# PCIe_USB30.net
KiCad netlist of a schematic drawn in Altium Designer
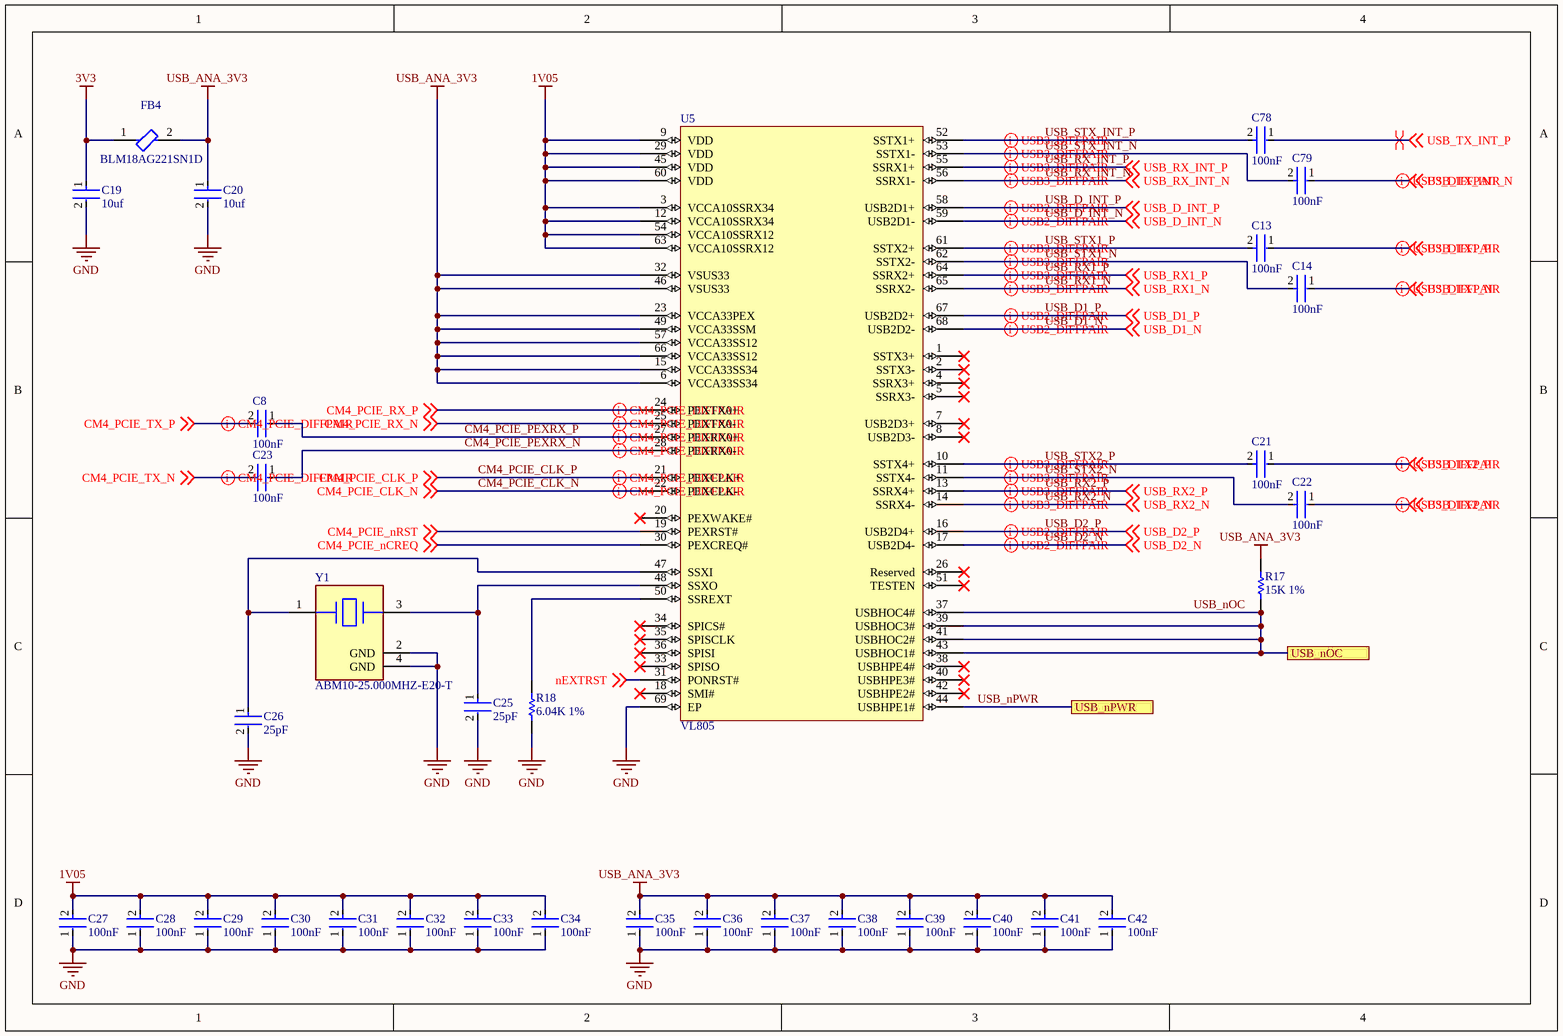
[diagram p0: PCIe_USB30.SchDoc]

(export (version "E")
  (design (tool "Eeschema 10.0.6"))
  (components
    (comp (ref "C8")
      (value "100nF")
      (footprint "FP-GRM15-MFG")
      (description "CAP CER 0.1UF 16V X7R 0402")
      (fields (field (name "MANUFACTURER PART NUMBER") "GRM155R71C104KA88D") (field (name "TOLERANCE") "10%"))
      (libsource (lib "Altium Content Vault") (part "236180d848d6139a670b325ea6854c9"))
    )
    (comp (ref "C13")
      (value "100nF")
      (footprint "FP-GRM15-MFG")
      (description "CAP CER 0.1UF 16V X7R 0402")
      (fields (field (name "MANUFACTURER PART NUMBER") "GRM155R71C104KA88D") (field (name "TOLERANCE") "10%"))
      (libsource (lib "Altium Content Vault") (part "236180d848d6139a670b325ea6854c9"))
    )
    (comp (ref "C14")
      (value "100nF")
      (footprint "FP-GRM15-MFG")
      (description "CAP CER 0.1UF 16V X7R 0402")
      (fields (field (name "MANUFACTURER PART NUMBER") "GRM155R71C104KA88D") (field (name "TOLERANCE") "10%"))
      (libsource (lib "Altium Content Vault") (part "236180d848d6139a670b325ea6854c9"))
    )
    (comp (ref "C19")
      (value "10uf")
      (footprint "FP-GRM188-0_2-IPC_C")
      (description "Chip Multilayer Ceramic Capacitors for General Purpose, 0603, 10uF, X5R, 15%, 20%, 35V")
      (fields (field (name "TOLERANCE") "20%"))
      (libsource (lib "Altium Content Vault") (part "11868f565c42a9108669ba33697ecf6"))
    )
    (comp (ref "C20")
      (value "10uf")
      (footprint "FP-GRM188-0_2-IPC_C")
      (description "Chip Multilayer Ceramic Capacitors for General Purpose, 0603, 10uF, X5R, 15%, 20%, 35V")
      (fields (field (name "TOLERANCE") "20%"))
      (libsource (lib "Altium Content Vault") (part "11868f565c42a9108669ba33697ecf6"))
    )
    (comp (ref "C21")
      (value "100nF")
      (footprint "FP-GRM15-MFG")
      (description "CAP CER 0.1UF 16V X7R 0402")
      (fields (field (name "MANUFACTURER PART NUMBER") "GRM155R71C104KA88D") (field (name "TOLERANCE") "10%"))
      (libsource (lib "Altium Content Vault") (part "236180d848d6139a670b325ea6854c9"))
    )
    (comp (ref "C22")
      (value "100nF")
      (footprint "FP-GRM15-MFG")
      (description "CAP CER 0.1UF 16V X7R 0402")
      (fields (field (name "MANUFACTURER PART NUMBER") "GRM155R71C104KA88D") (field (name "TOLERANCE") "10%"))
      (libsource (lib "Altium Content Vault") (part "236180d848d6139a670b325ea6854c9"))
    )
    (comp (ref "C23")
      (value "100nF")
      (footprint "FP-GRM15-MFG")
      (description "CAP CER 0.1UF 16V X7R 0402")
      (fields (field (name "MANUFACTURER PART NUMBER") "GRM155R71C104KA88D") (field (name "TOLERANCE") "10%"))
      (libsource (lib "Altium Content Vault") (part "236180d848d6139a670b325ea6854c9"))
    )
    (comp (ref "C25")
      (value "25pF")
      (footprint "FP-C0402-BB-MFG")
      (description "CAP CER 12PF 25V NP0 0402")
      (fields (field (name "MANUFACTURER") "Kemet") (field (name "TOLERANCE") "0.05"))
      (libsource (lib "Altium Content Vault") (part "b4654b650e69147ec39a6b967a45e02"))
    )
    (comp (ref "C26")
      (value "25pF")
      (footprint "FP-C0402-BB-MFG")
      (description "CAP CER 12PF 25V NP0 0402")
      (fields (field (name "MANUFACTURER") "Kemet") (field (name "TOLERANCE") "0.05"))
      (libsource (lib "Altium Content Vault") (part "b4654b650e69147ec39a6b967a45e02"))
    )
    (comp (ref "C27")
      (value "100nF")
      (footprint "FP-GRM15-MFG")
      (description "CAP CER 0.1UF 16V X7R 0402")
      (fields (field (name "MANUFACTURER PART NUMBER") "GRM155R71C104KA88D") (field (name "TOLERANCE") "10%"))
      (libsource (lib "Altium Content Vault") (part "236180d848d6139a670b325ea6854c9"))
    )
    (comp (ref "C28")
      (value "100nF")
      (footprint "FP-GRM15-MFG")
      (description "CAP CER 0.1UF 16V X7R 0402")
      (fields (field (name "MANUFACTURER PART NUMBER") "GRM155R71C104KA88D") (field (name "TOLERANCE") "10%"))
      (libsource (lib "Altium Content Vault") (part "236180d848d6139a670b325ea6854c9"))
    )
    (comp (ref "C29")
      (value "100nF")
      (footprint "FP-GRM15-MFG")
      (description "CAP CER 0.1UF 16V X7R 0402")
      (fields (field (name "MANUFACTURER PART NUMBER") "GRM155R71C104KA88D") (field (name "TOLERANCE") "10%"))
      (libsource (lib "Altium Content Vault") (part "236180d848d6139a670b325ea6854c9"))
    )
    (comp (ref "C30")
      (value "100nF")
      (footprint "FP-GRM15-MFG")
      (description "CAP CER 0.1UF 16V X7R 0402")
      (fields (field (name "MANUFACTURER PART NUMBER") "GRM155R71C104KA88D") (field (name "TOLERANCE") "10%"))
      (libsource (lib "Altium Content Vault") (part "236180d848d6139a670b325ea6854c9"))
    )
    (comp (ref "C31")
      (value "100nF")
      (footprint "FP-GRM15-MFG")
      (description "CAP CER 0.1UF 16V X7R 0402")
      (fields (field (name "MANUFACTURER PART NUMBER") "GRM155R71C104KA88D") (field (name "TOLERANCE") "10%"))
      (libsource (lib "Altium Content Vault") (part "236180d848d6139a670b325ea6854c9"))
    )
    (comp (ref "C32")
      (value "100nF")
      (footprint "FP-GRM15-MFG")
      (description "CAP CER 0.1UF 16V X7R 0402")
      (fields (field (name "MANUFACTURER PART NUMBER") "GRM155R71C104KA88D") (field (name "TOLERANCE") "10%"))
      (libsource (lib "Altium Content Vault") (part "236180d848d6139a670b325ea6854c9"))
    )
    (comp (ref "C33")
      (value "100nF")
      (footprint "FP-GRM15-MFG")
      (description "CAP CER 0.1UF 16V X7R 0402")
      (fields (field (name "MANUFACTURER PART NUMBER") "GRM155R71C104KA88D") (field (name "TOLERANCE") "10%"))
      (libsource (lib "Altium Content Vault") (part "236180d848d6139a670b325ea6854c9"))
    )
    (comp (ref "C34")
      (value "100nF")
      (footprint "FP-GRM15-MFG")
      (description "CAP CER 0.1UF 16V X7R 0402")
      (fields (field (name "MANUFACTURER PART NUMBER") "GRM155R71C104KA88D") (field (name "TOLERANCE") "10%"))
      (libsource (lib "Altium Content Vault") (part "236180d848d6139a670b325ea6854c9"))
    )
    (comp (ref "C35")
      (value "100nF")
      (footprint "FP-GRM15-MFG")
      (description "CAP CER 0.1UF 16V X7R 0402")
      (fields (field (name "MANUFACTURER PART NUMBER") "GRM155R71C104KA88D") (field (name "TOLERANCE") "10%"))
      (libsource (lib "Altium Content Vault") (part "236180d848d6139a670b325ea6854c9"))
    )
    (comp (ref "C36")
      (value "100nF")
      (footprint "FP-GRM15-MFG")
      (description "CAP CER 0.1UF 16V X7R 0402")
      (fields (field (name "MANUFACTURER PART NUMBER") "GRM155R71C104KA88D") (field (name "TOLERANCE") "10%"))
      (libsource (lib "Altium Content Vault") (part "236180d848d6139a670b325ea6854c9"))
    )
    (comp (ref "C37")
      (value "100nF")
      (footprint "FP-GRM15-MFG")
      (description "CAP CER 0.1UF 16V X7R 0402")
      (fields (field (name "MANUFACTURER PART NUMBER") "GRM155R71C104KA88D") (field (name "TOLERANCE") "10%"))
      (libsource (lib "Altium Content Vault") (part "236180d848d6139a670b325ea6854c9"))
    )
    (comp (ref "C38")
      (value "100nF")
      (footprint "FP-GRM15-MFG")
      (description "CAP CER 0.1UF 16V X7R 0402")
      (fields (field (name "MANUFACTURER PART NUMBER") "GRM155R71C104KA88D") (field (name "TOLERANCE") "10%"))
      (libsource (lib "Altium Content Vault") (part "236180d848d6139a670b325ea6854c9"))
    )
    (comp (ref "C39")
      (value "100nF")
      (footprint "FP-GRM15-MFG")
      (description "CAP CER 0.1UF 16V X7R 0402")
      (fields (field (name "MANUFACTURER PART NUMBER") "GRM155R71C104KA88D") (field (name "TOLERANCE") "10%"))
      (libsource (lib "Altium Content Vault") (part "236180d848d6139a670b325ea6854c9"))
    )
    (comp (ref "C40")
      (value "100nF")
      (footprint "FP-GRM15-MFG")
      (description "CAP CER 0.1UF 16V X7R 0402")
      (fields (field (name "MANUFACTURER PART NUMBER") "GRM155R71C104KA88D") (field (name "TOLERANCE") "10%"))
      (libsource (lib "Altium Content Vault") (part "236180d848d6139a670b325ea6854c9"))
    )
    (comp (ref "C41")
      (value "100nF")
      (footprint "FP-GRM15-MFG")
      (description "CAP CER 0.1UF 16V X7R 0402")
      (fields (field (name "MANUFACTURER PART NUMBER") "GRM155R71C104KA88D") (field (name "TOLERANCE") "10%"))
      (libsource (lib "Altium Content Vault") (part "236180d848d6139a670b325ea6854c9"))
    )
    (comp (ref "C42")
      (value "100nF")
      (footprint "FP-GRM15-MFG")
      (description "CAP CER 0.1UF 16V X7R 0402")
      (fields (field (name "MANUFACTURER PART NUMBER") "GRM155R71C104KA88D") (field (name "TOLERANCE") "10%"))
      (libsource (lib "Altium Content Vault") (part "236180d848d6139a670b325ea6854c9"))
    )
    (comp (ref "C78")
      (value "100nF")
      (footprint "FP-GRM15-MFG")
      (description "CAP CER 0.1UF 16V X7R 0402")
      (fields (field (name "MANUFACTURER PART NUMBER") "GRM155R71C104KA88D") (field (name "TOLERANCE") "10%"))
      (libsource (lib "Altium Content Vault") (part "236180d848d6139a670b325ea6854c9"))
    )
    (comp (ref "C79")
      (value "100nF")
      (footprint "FP-GRM15-MFG")
      (description "CAP CER 0.1UF 16V X7R 0402")
      (fields (field (name "MANUFACTURER PART NUMBER") "GRM155R71C104KA88D") (field (name "TOLERANCE") "10%"))
      (libsource (lib "Altium Content Vault") (part "236180d848d6139a670b325ea6854c9"))
    )
    (comp (ref "FB4")
      (value "BLM18AG221SN1D")
      (footprint "FP-BLM18-0_15-t0_8-IPC_A")
      (description "Chip Ferrite Bead, 0603, 220Ω @ 100MHz, 0.25Ω, 25%, 700mA")
      (fields (field (name "TOLERANCE") "25%"))
      (libsource (lib "Altium Content Vault") (part "5f30dd21d616792df468990f7003faa"))
    )
    (comp (ref "R17")
      (value "15K 1%")
      (footprint "RESC1005X40X25ML05T10")
      (fields (field (name "MANUFACTURER") "Yageo / Phycomp") (field (name "PART NUMBER") "RC0402FR0715KL"))
      (libsource (lib "Altium Content Vault") (part "RES"))
    )
    (comp (ref "R18")
      (value "6.04K 1%")
      (footprint "RESC1005X40X25LL05T10")
      (fields (field (name "PART NUMBER") "RC0402FR-076K04L") (field (name "MANUFACTURER") "Yageo"))
      (libsource (lib "Altium Content Vault") (part "RES"))
    )
    (comp (ref "U5") (value "VL805") (footprint "VL805") (libsource (lib "VL805") (part "VL805")))
    (comp (ref "Y1")
      (value "ABM10-25.000MHZ-E20-T")
      (footprint "FP-ABM10-MFG")
      (description "Crystal 25MHz ±20ppm 10pF SMD-4 2.5mm x 2mm")
      (fields (field (name "TOLERANCE") "20ppm"))
      (libsource (lib "Altium Content Vault") (part "0934ba461506c7e3a0bb4df7a4ed385"))
    )
  )
  (nets
    (net (code "1") (name "/CM4_PCIE_PEXRX_N") (class "Default")
      (node (ref "C23") (pin "1") (pinfunction "1_1") (pintype "passive"))
      (node (ref "U5") (pin "28") (pinfunction "PEXRX0-_28") (pintype "bidirectional"))
    )
    (net (code "2") (name "/CM4_PCIE_PEXRX_P") (class "Default")
      (node (ref "C8") (pin "1") (pinfunction "1_1") (pintype "passive"))
      (node (ref "U5") (pin "27") (pinfunction "PEXRX0+_27") (pintype "bidirectional"))
    )
    (net (code "3") (name "/USB_STX1_N") (class "Default")
      (node (ref "C14") (pin "2") (pinfunction "2_2") (pintype "passive"))
      (node (ref "U5") (pin "62") (pinfunction "SSTX2-_62") (pintype "bidirectional"))
    )
    (net (code "4") (name "/USB_STX1_P") (class "Default")
      (node (ref "C13") (pin "2") (pinfunction "2_2") (pintype "passive"))
      (node (ref "U5") (pin "61") (pinfunction "SSTX2+_61") (pintype "bidirectional"))
    )
    (net (code "5") (name "/USB_STX2_N") (class "Default")
      (node (ref "C22") (pin "2") (pinfunction "2_2") (pintype "passive"))
      (node (ref "U5") (pin "11") (pinfunction "SSTX4-_11") (pintype "bidirectional"))
    )
    (net (code "6") (name "/USB_STX2_P") (class "Default")
      (node (ref "C21") (pin "2") (pinfunction "2_2") (pintype "passive"))
      (node (ref "U5") (pin "10") (pinfunction "SSTX4+_10") (pintype "bidirectional"))
    )
    (net (code "7") (name "/USB_STX_INT_N") (class "Default")
      (node (ref "C79") (pin "2") (pinfunction "2_2") (pintype "passive"))
      (node (ref "U5") (pin "53") (pinfunction "SSTX1-_53") (pintype "bidirectional"))
    )
    (net (code "8") (name "/USB_STX_INT_P") (class "Default")
      (node (ref "C78") (pin "2") (pinfunction "2_2") (pintype "passive"))
      (node (ref "U5") (pin "52") (pinfunction "SSTX1+_52") (pintype "bidirectional"))
    )
    (net (code "9") (name "/USB_nOC") (class "Default")
      (node (ref "R17") (pin "1") (pinfunction "1_1") (pintype "passive"))
      (node (ref "U5") (pin "37") (pinfunction "USBHOC4#_37") (pintype "bidirectional"))
      (node (ref "U5") (pin "39") (pinfunction "USBHOC3#_39") (pintype "bidirectional"))
      (node (ref "U5") (pin "41") (pinfunction "USBHOC2#_41") (pintype "bidirectional"))
      (node (ref "U5") (pin "43") (pinfunction "USBHOC1#_43") (pintype "bidirectional"))
    )
    (net (code "10") (name "/USB_nPWR") (class "Default")
      (node (ref "U5") (pin "44") (pinfunction "USBHPE1#_44") (pintype "bidirectional"))
    )
    (net (code "11") (name "1V05") (class "Default")
      (node (ref "C27") (pin "2") (pinfunction "2_2") (pintype "passive"))
      (node (ref "C28") (pin "2") (pinfunction "2_2") (pintype "passive"))
      (node (ref "C29") (pin "2") (pinfunction "2_2") (pintype "passive"))
      (node (ref "C30") (pin "2") (pinfunction "2_2") (pintype "passive"))
      (node (ref "C31") (pin "2") (pinfunction "2_2") (pintype "passive"))
      (node (ref "C32") (pin "2") (pinfunction "2_2") (pintype "passive"))
      (node (ref "C33") (pin "2") (pinfunction "2_2") (pintype "passive"))
      (node (ref "C34") (pin "2") (pinfunction "2_2") (pintype "passive"))
      (node (ref "U5") (pin "12") (pinfunction "VCCA10SSRX34_12") (pintype "bidirectional"))
      (node (ref "U5") (pin "29") (pinfunction "VDD_29") (pintype "bidirectional"))
      (node (ref "U5") (pin "3") (pinfunction "VCCA10SSRX34_3") (pintype "bidirectional"))
      (node (ref "U5") (pin "45") (pinfunction "VDD_45") (pintype "bidirectional"))
      (node (ref "U5") (pin "54") (pinfunction "VCCA10SSRX12_54") (pintype "bidirectional"))
      (node (ref "U5") (pin "60") (pinfunction "VDD_60") (pintype "bidirectional"))
      (node (ref "U5") (pin "63") (pinfunction "VCCA10SSRX12_63") (pintype "bidirectional"))
      (node (ref "U5") (pin "9") (pinfunction "VDD_9") (pintype "bidirectional"))
    )
    (net (code "12") (name "3V3") (class "Default")
      (node (ref "C19") (pin "1") (pinfunction "1_1") (pintype "passive"))
      (node (ref "FB4") (pin "1") (pinfunction "1_1") (pintype "passive"))
    )
    (net (code "13") (name "CM4_PCIE_CLK_N") (class "Default")
      (node (ref "U5") (pin "22") (pinfunction "PEXCLK-_22") (pintype "bidirectional"))
    )
    (net (code "14") (name "CM4_PCIE_CLK_P") (class "Default")
      (node (ref "U5") (pin "21") (pinfunction "PEXCLK+_21") (pintype "bidirectional"))
    )
    (net (code "15") (name "CM4_PCIE_RX_N") (class "Default")
      (node (ref "U5") (pin "25") (pinfunction "PEXTX0-_25") (pintype "bidirectional"))
    )
    (net (code "16") (name "CM4_PCIE_RX_P") (class "Default")
      (node (ref "U5") (pin "24") (pinfunction "PEXTX0+_24") (pintype "bidirectional"))
    )
    (net (code "17") (name "CM4_PCIE_TX_N") (class "Default")
      (node (ref "C23") (pin "2") (pinfunction "2_2") (pintype "passive"))
    )
    (net (code "18") (name "CM4_PCIE_TX_P") (class "Default")
      (node (ref "C8") (pin "2") (pinfunction "2_2") (pintype "passive"))
    )
    (net (code "19") (name "CM4_PCIE_nCREQ") (class "Default")
      (node (ref "U5") (pin "30") (pinfunction "PEXCREQ#_30") (pintype "bidirectional"))
    )
    (net (code "20") (name "CM4_PCIE_nRST") (class "Default")
      (node (ref "U5") (pin "19") (pinfunction "PEXRST#_19") (pintype "bidirectional"))
    )
    (net (code "21") (name "GND") (class "Default")
      (node (ref "C19") (pin "2") (pinfunction "2_2") (pintype "passive"))
      (node (ref "C20") (pin "2") (pinfunction "2_2") (pintype "passive"))
      (node (ref "C25") (pin "2") (pinfunction "2_2") (pintype "passive"))
      (node (ref "C26") (pin "2") (pinfunction "2_2") (pintype "passive"))
      (node (ref "C27") (pin "1") (pinfunction "1_1") (pintype "passive"))
      (node (ref "C28") (pin "1") (pinfunction "1_1") (pintype "passive"))
      (node (ref "C29") (pin "1") (pinfunction "1_1") (pintype "passive"))
      (node (ref "C30") (pin "1") (pinfunction "1_1") (pintype "passive"))
      (node (ref "C31") (pin "1") (pinfunction "1_1") (pintype "passive"))
      (node (ref "C32") (pin "1") (pinfunction "1_1") (pintype "passive"))
      (node (ref "C33") (pin "1") (pinfunction "1_1") (pintype "passive"))
      (node (ref "C34") (pin "1") (pinfunction "1_1") (pintype "passive"))
      (node (ref "C35") (pin "1") (pinfunction "1_1") (pintype "passive"))
      (node (ref "C36") (pin "1") (pinfunction "1_1") (pintype "passive"))
      (node (ref "C37") (pin "1") (pinfunction "1_1") (pintype "passive"))
      (node (ref "C38") (pin "1") (pinfunction "1_1") (pintype "passive"))
      (node (ref "C39") (pin "1") (pinfunction "1_1") (pintype "passive"))
      (node (ref "C40") (pin "1") (pinfunction "1_1") (pintype "passive"))
      (node (ref "C41") (pin "1") (pinfunction "1_1") (pintype "passive"))
      (node (ref "C42") (pin "1") (pinfunction "1_1") (pintype "passive"))
      (node (ref "R18") (pin "1") (pinfunction "1_1") (pintype "passive"))
      (node (ref "U5") (pin "69") (pinfunction "EP_69") (pintype "bidirectional"))
      (node (ref "Y1") (pin "2") (pinfunction "GND_2") (pintype "power_in"))
      (node (ref "Y1") (pin "4") (pinfunction "GND_4") (pintype "power_in"))
    )
    (net (code "22") (name "Net-(U5-SSREXT)") (class "Default")
      (node (ref "R18") (pin "2") (pinfunction "2_2") (pintype "passive"))
      (node (ref "U5") (pin "50") (pinfunction "SSREXT_50") (pintype "bidirectional"))
    )
    (net (code "23") (name "Net-(U5-SSXI)") (class "Default")
      (node (ref "C26") (pin "1") (pinfunction "1_1") (pintype "passive"))
      (node (ref "U5") (pin "47") (pinfunction "SSXI_47") (pintype "bidirectional"))
      (node (ref "Y1") (pin "1") (pinfunction "1_1") (pintype "passive"))
    )
    (net (code "24") (name "Net-(U5-SSXO)") (class "Default")
      (node (ref "C25") (pin "1") (pinfunction "1_1") (pintype "passive"))
      (node (ref "U5") (pin "48") (pinfunction "SSXO_48") (pintype "bidirectional"))
      (node (ref "Y1") (pin "3") (pinfunction "3_3") (pintype "passive"))
    )
    (net (code "25") (name "USB_ANA_3V3") (class "Default")
      (node (ref "C20") (pin "1") (pinfunction "1_1") (pintype "passive"))
      (node (ref "C35") (pin "2") (pinfunction "2_2") (pintype "passive"))
      (node (ref "C36") (pin "2") (pinfunction "2_2") (pintype "passive"))
      (node (ref "C37") (pin "2") (pinfunction "2_2") (pintype "passive"))
      (node (ref "C38") (pin "2") (pinfunction "2_2") (pintype "passive"))
      (node (ref "C39") (pin "2") (pinfunction "2_2") (pintype "passive"))
      (node (ref "C40") (pin "2") (pinfunction "2_2") (pintype "passive"))
      (node (ref "C41") (pin "2") (pinfunction "2_2") (pintype "passive"))
      (node (ref "C42") (pin "2") (pinfunction "2_2") (pintype "passive"))
      (node (ref "FB4") (pin "2") (pinfunction "2_2") (pintype "passive"))
      (node (ref "R17") (pin "2") (pinfunction "2_2") (pintype "passive"))
      (node (ref "U5") (pin "15") (pinfunction "VCCA33SS34_15") (pintype "bidirectional"))
      (node (ref "U5") (pin "23") (pinfunction "VCCA33PEX_23") (pintype "bidirectional"))
      (node (ref "U5") (pin "32") (pinfunction "VSUS33_32") (pintype "bidirectional"))
      (node (ref "U5") (pin "46") (pinfunction "VSUS33_46") (pintype "bidirectional"))
      (node (ref "U5") (pin "49") (pinfunction "VCCA33SSM_49") (pintype "bidirectional"))
      (node (ref "U5") (pin "57") (pinfunction "VCCA33SS12_57") (pintype "bidirectional"))
      (node (ref "U5") (pin "6") (pinfunction "VCCA33SS34_6") (pintype "bidirectional"))
      (node (ref "U5") (pin "66") (pinfunction "VCCA33SS12_66") (pintype "bidirectional"))
    )
    (net (code "26") (name "USB_D1_N") (class "Default")
      (node (ref "U5") (pin "68") (pinfunction "USB2D2-_68") (pintype "bidirectional"))
    )
    (net (code "27") (name "USB_D1_P") (class "Default")
      (node (ref "U5") (pin "67") (pinfunction "USB2D2+_67") (pintype "bidirectional"))
    )
    (net (code "28") (name "USB_D2_N") (class "Default")
      (node (ref "U5") (pin "17") (pinfunction "USB2D4-_17") (pintype "bidirectional"))
    )
    (net (code "29") (name "USB_D2_P") (class "Default")
      (node (ref "U5") (pin "16") (pinfunction "USB2D4+_16") (pintype "bidirectional"))
    )
    (net (code "30") (name "USB_D_INT_N") (class "Default")
      (node (ref "U5") (pin "59") (pinfunction "USB2D1-_59") (pintype "bidirectional"))
    )
    (net (code "31") (name "USB_D_INT_P") (class "Default")
      (node (ref "U5") (pin "58") (pinfunction "USB2D1+_58") (pintype "bidirectional"))
    )
    (net (code "32") (name "USB_RX1_N") (class "Default")
      (node (ref "U5") (pin "65") (pinfunction "SSRX2-_65") (pintype "bidirectional"))
    )
    (net (code "33") (name "USB_RX1_P") (class "Default")
      (node (ref "U5") (pin "64") (pinfunction "SSRX2+_64") (pintype "bidirectional"))
    )
    (net (code "34") (name "USB_RX2_N") (class "Default")
      (node (ref "U5") (pin "14") (pinfunction "SSRX4-_14") (pintype "bidirectional"))
    )
    (net (code "35") (name "USB_RX2_P") (class "Default")
      (node (ref "U5") (pin "13") (pinfunction "SSRX4+_13") (pintype "bidirectional"))
    )
    (net (code "36") (name "USB_RX_INT_N") (class "Default")
      (node (ref "U5") (pin "56") (pinfunction "SSRX1-_56") (pintype "bidirectional"))
    )
    (net (code "37") (name "USB_RX_INT_P") (class "Default")
      (node (ref "U5") (pin "55") (pinfunction "SSRX1+_55") (pintype "bidirectional"))
    )
    (net (code "38") (name "USB_TX1_N") (class "Default")
      (node (ref "C14") (pin "1") (pinfunction "1_1") (pintype "passive"))
    )
    (net (code "39") (name "USB_TX1_P") (class "Default")
      (node (ref "C13") (pin "1") (pinfunction "1_1") (pintype "passive"))
    )
    (net (code "40") (name "USB_TX2_N") (class "Default")
      (node (ref "C22") (pin "1") (pinfunction "1_1") (pintype "passive"))
    )
    (net (code "41") (name "USB_TX2_P") (class "Default")
      (node (ref "C21") (pin "1") (pinfunction "1_1") (pintype "passive"))
    )
    (net (code "42") (name "USB_TX_INT_N") (class "Default")
      (node (ref "C79") (pin "1") (pinfunction "1_1") (pintype "passive"))
    )
    (net (code "43") (name "USB_TX_INT_P") (class "Default")
      (node (ref "C78") (pin "1") (pinfunction "1_1") (pintype "passive"))
    )
    (net (code "44") (name "nEXTRST") (class "Default")
      (node (ref "U5") (pin "31") (pinfunction "PONRST#_31") (pintype "bidirectional"))
    )
    (net (code "45") (name "unconnected-(U5-PEXWAKE#-Pad20)") (class "Default")
      (node (ref "U5") (pin "20") (pinfunction "PEXWAKE#_20") (pintype "bidirectional+no_connect"))
    )
    (net (code "46") (name "unconnected-(U5-Reserved-Pad26)") (class "Default")
      (node (ref "U5") (pin "26") (pinfunction "Reserved_26") (pintype "bidirectional+no_connect"))
    )
    (net (code "47") (name "unconnected-(U5-SMI#-Pad18)") (class "Default")
      (node (ref "U5") (pin "18") (pinfunction "SMI#_18") (pintype "bidirectional+no_connect"))
    )
    (net (code "48") (name "unconnected-(U5-SPICS#-Pad34)") (class "Default")
      (node (ref "U5") (pin "34") (pinfunction "SPICS#_34") (pintype "bidirectional+no_connect"))
    )
    (net (code "49") (name "unconnected-(U5-SPISCLK-Pad35)") (class "Default")
      (node (ref "U5") (pin "35") (pinfunction "SPISCLK_35") (pintype "bidirectional+no_connect"))
    )
    (net (code "50") (name "unconnected-(U5-SPISI-Pad36)") (class "Default")
      (node (ref "U5") (pin "36") (pinfunction "SPISI_36") (pintype "bidirectional+no_connect"))
    )
    (net (code "51") (name "unconnected-(U5-SPISO-Pad33)") (class "Default")
      (node (ref "U5") (pin "33") (pinfunction "SPISO_33") (pintype "bidirectional+no_connect"))
    )
    (net (code "52") (name "unconnected-(U5-SSRX3+-Pad4)") (class "Default")
      (node (ref "U5") (pin "4") (pinfunction "SSRX3+_4") (pintype "bidirectional+no_connect"))
    )
    (net (code "53") (name "unconnected-(U5-SSRX3--Pad5)") (class "Default")
      (node (ref "U5") (pin "5") (pinfunction "SSRX3-_5") (pintype "bidirectional+no_connect"))
    )
    (net (code "54") (name "unconnected-(U5-SSTX3+-Pad1)") (class "Default")
      (node (ref "U5") (pin "1") (pinfunction "SSTX3+_1") (pintype "bidirectional+no_connect"))
    )
    (net (code "55") (name "unconnected-(U5-SSTX3--Pad2)") (class "Default")
      (node (ref "U5") (pin "2") (pinfunction "SSTX3-_2") (pintype "bidirectional+no_connect"))
    )
    (net (code "56") (name "unconnected-(U5-TESTEN-Pad51)") (class "Default")
      (node (ref "U5") (pin "51") (pinfunction "TESTEN_51") (pintype "bidirectional+no_connect"))
    )
    (net (code "57") (name "unconnected-(U5-USB2D3+-Pad7)") (class "Default")
      (node (ref "U5") (pin "7") (pinfunction "USB2D3+_7") (pintype "bidirectional+no_connect"))
    )
    (net (code "58") (name "unconnected-(U5-USB2D3--Pad8)") (class "Default")
      (node (ref "U5") (pin "8") (pinfunction "USB2D3-_8") (pintype "bidirectional+no_connect"))
    )
    (net (code "59") (name "unconnected-(U5-USBHPE2#-Pad42)") (class "Default")
      (node (ref "U5") (pin "42") (pinfunction "USBHPE2#_42") (pintype "bidirectional+no_connect"))
    )
    (net (code "60") (name "unconnected-(U5-USBHPE3#-Pad40)") (class "Default")
      (node (ref "U5") (pin "40") (pinfunction "USBHPE3#_40") (pintype "bidirectional+no_connect"))
    )
    (net (code "61") (name "unconnected-(U5-USBHPE4#-Pad38)") (class "Default")
      (node (ref "U5") (pin "38") (pinfunction "USBHPE4#_38") (pintype "bidirectional+no_connect"))
    )
  )
)
